# YosanoLoveButton.net
KiCad netlist of a schematic drawn in EAGLE
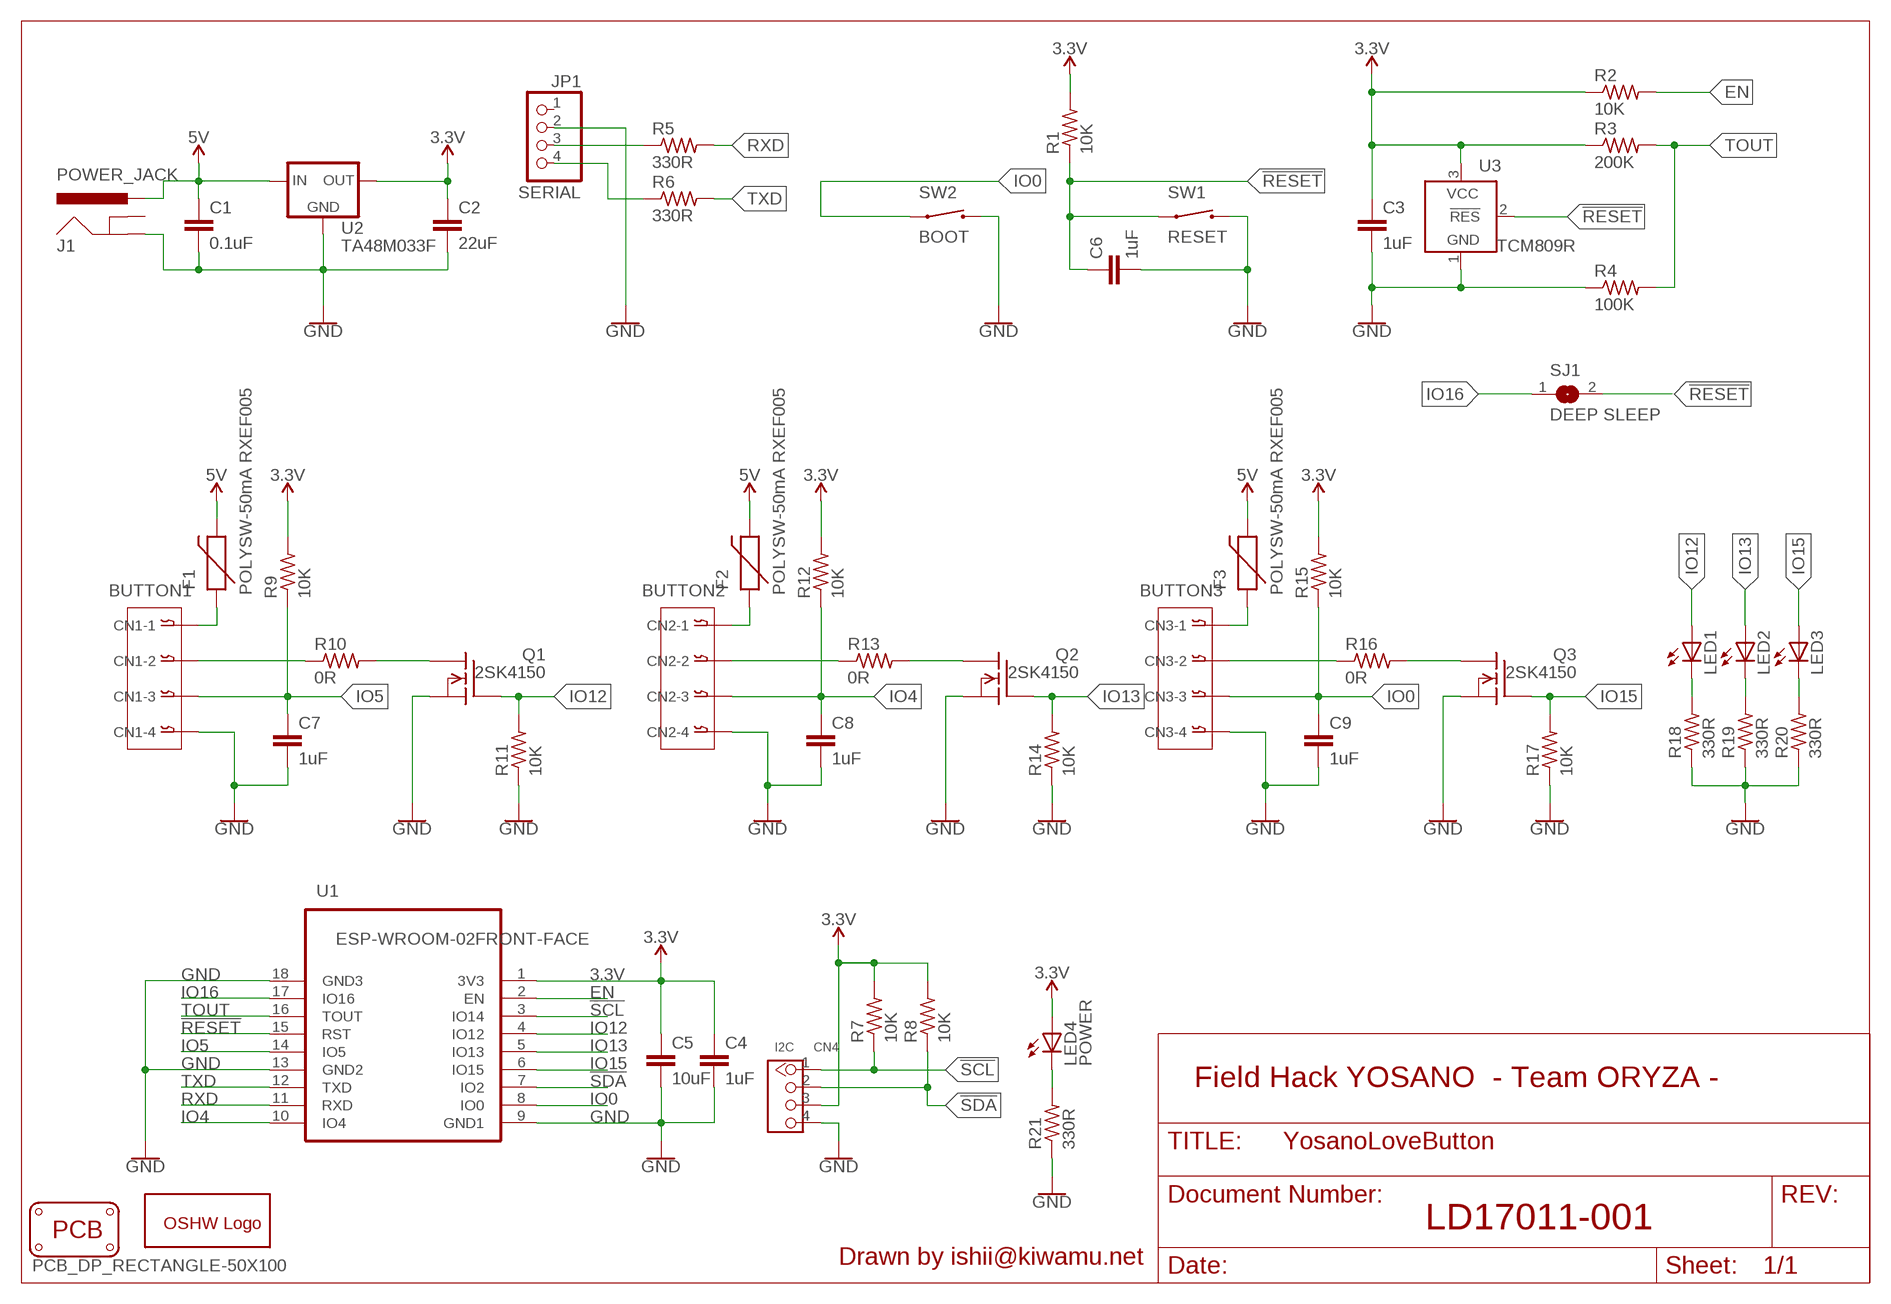
[diagram p0: schematic, sheet 1]

(export (version "E")
  (design (tool "Eeschema 10.0.6"))
  (components
    (comp (ref "C1")
      (value "0.1uF")
      (footprint "eagle-import:C5B2.5")
      (libsource (lib "eagle-import") (part "C5/2.5"))
    )
    (comp (ref "C2")
      (value "22uF")
      (footprint "eagle-import:C5B2.5")
      (libsource (lib "eagle-import") (part "C5/2.5"))
    )
    (comp (ref "C3")
      (value "1uF")
      (footprint "eagle-import:C5B2.5")
      (libsource (lib "eagle-import") (part "C5/2.5"))
    )
    (comp (ref "C4")
      (value "1uF")
      (footprint "eagle-import:C5B2.5")
      (libsource (lib "eagle-import") (part "C5/2.5"))
    )
    (comp (ref "C5")
      (value "10uF")
      (footprint "eagle-import:C5B2.5")
      (libsource (lib "eagle-import") (part "C5/2.5"))
    )
    (comp (ref "C6")
      (value "1uF")
      (footprint "eagle-import:C5B2.5")
      (libsource (lib "eagle-import") (part "C5/2.5"))
    )
    (comp (ref "C7")
      (value "1uF")
      (footprint "eagle-import:C5B2.5")
      (libsource (lib "eagle-import") (part "C5/2.5"))
    )
    (comp (ref "C8")
      (value "1uF")
      (footprint "eagle-import:C5B2.5")
      (libsource (lib "eagle-import") (part "C5/2.5"))
    )
    (comp (ref "C9")
      (value "1uF")
      (footprint "eagle-import:C5B2.5")
      (libsource (lib "eagle-import") (part "C5/2.5"))
    )
    (comp (ref "CN1")
      (value "BUTTON1")
      (footprint "eagle-import:B4B-XH")
      (libsource (lib "eagle-import") (part "04-JST-B4B-XH-A"))
    )
    (comp (ref "CN2")
      (value "BUTTON2")
      (footprint "eagle-import:B4B-XH")
      (libsource (lib "eagle-import") (part "04-JST-B4B-XH-A"))
    )
    (comp (ref "CN3")
      (value "BUTTON3")
      (footprint "eagle-import:B4B-XH")
      (libsource (lib "eagle-import") (part "04-JST-B4B-XH-A"))
    )
    (comp (ref "CN4")
      (value "I2C")
      (footprint "eagle-import:HW4-2.0")
      (libsource (lib "eagle-import") (part "GROVE-CONNECTOR-DIP(4P-2.0)"))
    )
    (comp (ref "F1")
      (value "POLYSW-50mA RXEF005")
      (footprint "eagle-import:PTC")
      (libsource (lib "eagle-import") (part "PTCPTH"))
    )
    (comp (ref "F2")
      (value "POLYSW-50mA RXEF005")
      (footprint "eagle-import:PTC")
      (libsource (lib "eagle-import") (part "PTCPTH"))
    )
    (comp (ref "F3")
      (value "POLYSW-50mA RXEF005")
      (footprint "eagle-import:PTC")
      (libsource (lib "eagle-import") (part "PTCPTH"))
    )
    (comp (ref "GOLD_ORB_SM1")
      (value "OSHWLOGOLOGO5MM")
      (footprint "eagle-import:OSHW_5MM")
      (libsource (lib "eagle-import") (part "OSHWLOGOLOGO5MM"))
    )
    (comp (ref "J1")
      (value "POWER_JACK")
      (footprint "eagle-import:POWER_JACK_PTH")
      (libsource (lib "eagle-import") (part "POWER_JACK"))
    )
    (comp (ref "JP1")
      (value "SERIAL")
      (footprint "eagle-import:1X04")
      (libsource (lib "eagle-import") (part "PINHD-1X4"))
    )
    (comp (ref "LED1")
      (value "LED3MM")
      (footprint "eagle-import:LED3MM")
      (libsource (lib "eagle-import") (part "LED3MM"))
    )
    (comp (ref "LED2")
      (value "LED3MM")
      (footprint "eagle-import:LED3MM")
      (libsource (lib "eagle-import") (part "LED3MM"))
    )
    (comp (ref "LED3")
      (value "LED3MM")
      (footprint "eagle-import:LED3MM")
      (libsource (lib "eagle-import") (part "LED3MM"))
    )
    (comp (ref "LED4")
      (value "POWER")
      (footprint "eagle-import:LED3MM")
      (libsource (lib "eagle-import") (part "LED3MM"))
    )
    (comp (ref "PCB1")
      (value "PCB_DP_RECTANGLE-50X100")
      (footprint "eagle-import:DP10050_V1")
      (libsource (lib "eagle-import") (part "PCB_DP_RECTANGLE-50X100"))
    )
    (comp (ref "Q1")
      (value "2SK4150")
      (footprint "eagle-import:TO92")
      (libsource (lib "eagle-import") (part "BSS101"))
    )
    (comp (ref "Q2")
      (value "2SK4150")
      (footprint "eagle-import:TO92")
      (libsource (lib "eagle-import") (part "BSS101"))
    )
    (comp (ref "Q3")
      (value "2SK4150")
      (footprint "eagle-import:TO92")
      (libsource (lib "eagle-import") (part "BSS101"))
    )
    (comp (ref "R1")
      (value "10K")
      (footprint "eagle-import:0204_7")
      (libsource (lib "eagle-import") (part "R-US_0204/7"))
    )
    (comp (ref "R2")
      (value "10K")
      (footprint "eagle-import:0204_7")
      (libsource (lib "eagle-import") (part "R-US_0204/7"))
    )
    (comp (ref "R3")
      (value "200K")
      (footprint "eagle-import:0204_7")
      (libsource (lib "eagle-import") (part "R-US_0204/7"))
    )
    (comp (ref "R4")
      (value "100K")
      (footprint "eagle-import:0204_7")
      (libsource (lib "eagle-import") (part "R-US_0204/7"))
    )
    (comp (ref "R5")
      (value "330R")
      (footprint "eagle-import:0204_7")
      (libsource (lib "eagle-import") (part "R-US_0204/7"))
    )
    (comp (ref "R6")
      (value "330R")
      (footprint "eagle-import:0204_7")
      (libsource (lib "eagle-import") (part "R-US_0204/7"))
    )
    (comp (ref "R7")
      (value "10K")
      (footprint "eagle-import:0204_7")
      (libsource (lib "eagle-import") (part "R-US_0204/7"))
    )
    (comp (ref "R8")
      (value "10K")
      (footprint "eagle-import:0204_7")
      (libsource (lib "eagle-import") (part "R-US_0204/7"))
    )
    (comp (ref "R9")
      (value "10K")
      (footprint "eagle-import:0204_7")
      (libsource (lib "eagle-import") (part "R-US_0204/7"))
    )
    (comp (ref "R10")
      (value "0R")
      (footprint "eagle-import:0204_7")
      (libsource (lib "eagle-import") (part "R-US_0204/7"))
    )
    (comp (ref "R11")
      (value "10K")
      (footprint "eagle-import:0204_7")
      (libsource (lib "eagle-import") (part "R-US_0204/7"))
    )
    (comp (ref "R12")
      (value "10K")
      (footprint "eagle-import:0204_7")
      (libsource (lib "eagle-import") (part "R-US_0204/7"))
    )
    (comp (ref "R13")
      (value "0R")
      (footprint "eagle-import:0204_7")
      (libsource (lib "eagle-import") (part "R-US_0204/7"))
    )
    (comp (ref "R14")
      (value "10K")
      (footprint "eagle-import:0204_7")
      (libsource (lib "eagle-import") (part "R-US_0204/7"))
    )
    (comp (ref "R15")
      (value "10K")
      (footprint "eagle-import:0204_7")
      (libsource (lib "eagle-import") (part "R-US_0204/7"))
    )
    (comp (ref "R16")
      (value "0R")
      (footprint "eagle-import:0204_7")
      (libsource (lib "eagle-import") (part "R-US_0204/7"))
    )
    (comp (ref "R17")
      (value "10K")
      (footprint "eagle-import:0204_7")
      (libsource (lib "eagle-import") (part "R-US_0204/7"))
    )
    (comp (ref "R18")
      (value "330R")
      (footprint "eagle-import:0204_7")
      (libsource (lib "eagle-import") (part "R-US_0204/7"))
    )
    (comp (ref "R19")
      (value "330R")
      (footprint "eagle-import:0204_7")
      (libsource (lib "eagle-import") (part "R-US_0204/7"))
    )
    (comp (ref "R20")
      (value "330R")
      (footprint "eagle-import:0204_7")
      (libsource (lib "eagle-import") (part "R-US_0204/7"))
    )
    (comp (ref "R21")
      (value "330R")
      (footprint "eagle-import:0204_7")
      (libsource (lib "eagle-import") (part "R-US_0204/7"))
    )
    (comp (ref "SJ1")
      (value "DEEP SLEEP")
      (footprint "eagle-import:SOLDERJUMPER_REFLOW")
      (libsource (lib "eagle-import") (part "SOLDERJUMPERREFLOW"))
    )
    (comp (ref "SW1")
      (value "RESET")
      (footprint "eagle-import:TVBP06")
      (libsource (lib "eagle-import") (part "TVBP06"))
    )
    (comp (ref "SW2")
      (value "BOOT")
      (footprint "eagle-import:TVBP06")
      (libsource (lib "eagle-import") (part "TVBP06"))
    )
    (comp (ref "U1")
      (value "ESP-WROOM-02FRONT-FACE")
      (footprint "eagle-import:FRONT-FACE")
      (libsource (lib "eagle-import") (part "ESP-WROOM-02FRONT-FACE"))
    )
    (comp (ref "U2")
      (value "TA48M033F")
      (footprint "eagle-import:DPACK")
      (libsource (lib "eagle-import") (part "TA48?M033F"))
    )
    (comp (ref "U3")
      (value "TCM809R")
      (footprint "eagle-import:SOT23B-3")
      (fields (field (name "MF") "MICROCHIP") (field (name "MPN") "TCM809MENB713"))
      (libsource (lib "eagle-import") (part "TCM809"))
    )
  )
  (nets
    (net (code "1") (name "/~{RESET}") (class "Default")
      (node (ref "C6") (pin "1") (pinfunction "1_1") (pintype "passive"))
      (node (ref "R1") (pin "1") (pinfunction "1_1") (pintype "passive"))
      (node (ref "SJ1") (pin "2") (pinfunction "2_2") (pintype "passive"))
      (node (ref "SW1") (pin "1") (pinfunction "1_1") (pintype "passive"))
      (node (ref "U1") (pin "15") (pinfunction "RST_15") (pintype "bidirectional"))
      (node (ref "U3") (pin "2") (pinfunction "~{RES}_2") (pintype "output"))
    )
    (net (code "2") (name "/~{SCL}") (class "Default")
      (node (ref "CN4") (pin "1") (pinfunction "1_1") (pintype "bidirectional"))
      (node (ref "R7") (pin "1") (pinfunction "1_1") (pintype "passive"))
      (node (ref "U1") (pin "3") (pinfunction "IO14_3") (pintype "bidirectional"))
    )
    (net (code "3") (name "/~{SDA}") (class "Default")
      (node (ref "CN4") (pin "2") (pinfunction "2_2") (pintype "bidirectional"))
      (node (ref "R8") (pin "1") (pinfunction "1_1") (pintype "passive"))
      (node (ref "U1") (pin "7") (pinfunction "IO2_7") (pintype "bidirectional"))
    )
    (net (code "4") (name "3.3V") (class "Default")
      (node (ref "C2") (pin "1") (pinfunction "1_1") (pintype "passive"))
      (node (ref "C3") (pin "1") (pinfunction "1_1") (pintype "passive"))
      (node (ref "C4") (pin "1") (pinfunction "1_1") (pintype "passive"))
      (node (ref "C5") (pin "1") (pinfunction "1_1") (pintype "passive"))
      (node (ref "CN4") (pin "3") (pinfunction "3_3") (pintype "bidirectional"))
      (node (ref "LED4") (pin "A") (pinfunction "A_A") (pintype "passive"))
      (node (ref "R1") (pin "2") (pinfunction "2_2") (pintype "passive"))
      (node (ref "R12") (pin "2") (pinfunction "2_2") (pintype "passive"))
      (node (ref "R15") (pin "2") (pinfunction "2_2") (pintype "passive"))
      (node (ref "R2") (pin "1") (pinfunction "1_1") (pintype "passive"))
      (node (ref "R3") (pin "1") (pinfunction "1_1") (pintype "passive"))
      (node (ref "R7") (pin "2") (pinfunction "2_2") (pintype "passive"))
      (node (ref "R8") (pin "2") (pinfunction "2_2") (pintype "passive"))
      (node (ref "R9") (pin "2") (pinfunction "2_2") (pintype "passive"))
      (node (ref "U1") (pin "1") (pinfunction "3V3_1") (pintype "power_in"))
      (node (ref "U2") (pin "3") (pinfunction "OUT_3") (pintype "passive"))
      (node (ref "U3") (pin "3") (pinfunction "VCC_3") (pintype "power_in"))
    )
    (net (code "5") (name "5V") (class "Default")
      (node (ref "C1") (pin "1") (pinfunction "1_1") (pintype "passive"))
      (node (ref "F1") (pin "P$2") (pinfunction "2_P$2") (pintype "bidirectional"))
      (node (ref "F2") (pin "P$2") (pinfunction "2_P$2") (pintype "bidirectional"))
      (node (ref "F3") (pin "P$2") (pinfunction "2_P$2") (pintype "bidirectional"))
      (node (ref "J1") (pin "PWR") (pinfunction "PWR_PWR") (pintype "bidirectional"))
      (node (ref "U2") (pin "1") (pinfunction "IN_1") (pintype "input"))
    )
    (net (code "6") (name "EN") (class "Default")
      (node (ref "R2") (pin "2") (pinfunction "2_2") (pintype "passive"))
      (node (ref "U1") (pin "2") (pinfunction "EN_2") (pintype "bidirectional"))
    )
    (net (code "7") (name "GND") (class "Default")
      (node (ref "C1") (pin "2") (pinfunction "2_2") (pintype "passive"))
      (node (ref "C2") (pin "2") (pinfunction "2_2") (pintype "passive"))
      (node (ref "C3") (pin "2") (pinfunction "2_2") (pintype "passive"))
      (node (ref "C4") (pin "2") (pinfunction "2_2") (pintype "passive"))
      (node (ref "C5") (pin "2") (pinfunction "2_2") (pintype "passive"))
      (node (ref "C6") (pin "2") (pinfunction "2_2") (pintype "passive"))
      (node (ref "C7") (pin "2") (pinfunction "2_2") (pintype "passive"))
      (node (ref "C8") (pin "2") (pinfunction "2_2") (pintype "passive"))
      (node (ref "C9") (pin "2") (pinfunction "2_2") (pintype "passive"))
      (node (ref "CN1") (pin "P$4") (pinfunction "1_P$4") (pintype "passive"))
      (node (ref "CN2") (pin "P$4") (pinfunction "1_P$4") (pintype "passive"))
      (node (ref "CN3") (pin "P$4") (pinfunction "1_P$4") (pintype "passive"))
      (node (ref "CN4") (pin "4") (pinfunction "4_4") (pintype "bidirectional"))
      (node (ref "J1") (pin "GND") (pinfunction "GND_GND") (pintype "bidirectional"))
      (node (ref "JP1") (pin "2") (pinfunction "2_2") (pintype "passive"))
      (node (ref "Q1") (pin "1") (pinfunction "S_1") (pintype "passive"))
      (node (ref "Q2") (pin "1") (pinfunction "S_1") (pintype "passive"))
      (node (ref "Q3") (pin "1") (pinfunction "S_1") (pintype "passive"))
      (node (ref "R11") (pin "1") (pinfunction "1_1") (pintype "passive"))
      (node (ref "R14") (pin "1") (pinfunction "1_1") (pintype "passive"))
      (node (ref "R17") (pin "1") (pinfunction "1_1") (pintype "passive"))
      (node (ref "R18") (pin "1") (pinfunction "1_1") (pintype "passive"))
      (node (ref "R19") (pin "1") (pinfunction "1_1") (pintype "passive"))
      (node (ref "R20") (pin "1") (pinfunction "1_1") (pintype "passive"))
      (node (ref "R21") (pin "1") (pinfunction "1_1") (pintype "passive"))
      (node (ref "R4") (pin "1") (pinfunction "1_1") (pintype "passive"))
      (node (ref "SW1") (pin "2") (pinfunction "2_2") (pintype "passive"))
      (node (ref "SW2") (pin "2") (pinfunction "2_2") (pintype "passive"))
      (node (ref "U1") (pin "13") (pinfunction "GND2_13") (pintype "power_in"))
      (node (ref "U1") (pin "18") (pinfunction "GND3_18") (pintype "power_in"))
      (node (ref "U1") (pin "9") (pinfunction "GND1_9") (pintype "power_in"))
      (node (ref "U2") (pin "4") (pinfunction "GND_4") (pintype "power_in"))
      (node (ref "U3") (pin "1") (pinfunction "GND_1") (pintype "power_in"))
    )
    (net (code "8") (name "IO0") (class "Default")
      (node (ref "C9") (pin "1") (pinfunction "1_1") (pintype "passive"))
      (node (ref "CN3") (pin "P$3") (pinfunction "1_P$3") (pintype "passive"))
      (node (ref "R15") (pin "1") (pinfunction "1_1") (pintype "passive"))
      (node (ref "SW2") (pin "1") (pinfunction "1_1") (pintype "passive"))
      (node (ref "U1") (pin "8") (pinfunction "IO0_8") (pintype "bidirectional"))
    )
    (net (code "9") (name "IO4") (class "Default")
      (node (ref "C8") (pin "1") (pinfunction "1_1") (pintype "passive"))
      (node (ref "CN2") (pin "P$3") (pinfunction "1_P$3") (pintype "passive"))
      (node (ref "R12") (pin "1") (pinfunction "1_1") (pintype "passive"))
      (node (ref "U1") (pin "10") (pinfunction "IO4_10") (pintype "bidirectional"))
    )
    (net (code "10") (name "IO5") (class "Default")
      (node (ref "C7") (pin "1") (pinfunction "1_1") (pintype "passive"))
      (node (ref "CN1") (pin "P$3") (pinfunction "1_P$3") (pintype "passive"))
      (node (ref "R9") (pin "1") (pinfunction "1_1") (pintype "passive"))
      (node (ref "U1") (pin "14") (pinfunction "IO5_14") (pintype "open_collector"))
    )
    (net (code "11") (name "IO12") (class "Default")
      (node (ref "LED1") (pin "A") (pinfunction "A_A") (pintype "passive"))
      (node (ref "Q1") (pin "2") (pinfunction "G_2") (pintype "passive"))
      (node (ref "R11") (pin "2") (pinfunction "2_2") (pintype "passive"))
      (node (ref "U1") (pin "4") (pinfunction "IO12_4") (pintype "bidirectional"))
    )
    (net (code "12") (name "IO13") (class "Default")
      (node (ref "LED2") (pin "A") (pinfunction "A_A") (pintype "passive"))
      (node (ref "Q2") (pin "2") (pinfunction "G_2") (pintype "passive"))
      (node (ref "R14") (pin "2") (pinfunction "2_2") (pintype "passive"))
      (node (ref "U1") (pin "5") (pinfunction "IO13_5") (pintype "bidirectional"))
    )
    (net (code "13") (name "IO15") (class "Default")
      (node (ref "LED3") (pin "A") (pinfunction "A_A") (pintype "passive"))
      (node (ref "Q3") (pin "2") (pinfunction "G_2") (pintype "passive"))
      (node (ref "R17") (pin "2") (pinfunction "2_2") (pintype "passive"))
      (node (ref "U1") (pin "6") (pinfunction "IO15_6") (pintype "bidirectional"))
    )
    (net (code "14") (name "IO16") (class "Default")
      (node (ref "SJ1") (pin "1") (pinfunction "1_1") (pintype "passive"))
      (node (ref "U1") (pin "17") (pinfunction "IO16_17") (pintype "bidirectional"))
    )
    (net (code "15") (name "Net-(CN1A-1)") (class "Default")
      (node (ref "CN1") (pin "P$1") (pinfunction "1_P$1") (pintype "passive"))
      (node (ref "F1") (pin "P$1") (pinfunction "1_P$1") (pintype "bidirectional"))
    )
    (net (code "16") (name "Net-(CN1B-1)") (class "Default")
      (node (ref "CN1") (pin "P$2") (pinfunction "1_P$2") (pintype "passive"))
      (node (ref "R10") (pin "1") (pinfunction "1_1") (pintype "passive"))
    )
    (net (code "17") (name "Net-(CN2A-1)") (class "Default")
      (node (ref "CN2") (pin "P$1") (pinfunction "1_P$1") (pintype "passive"))
      (node (ref "F2") (pin "P$1") (pinfunction "1_P$1") (pintype "bidirectional"))
    )
    (net (code "18") (name "Net-(CN2B-1)") (class "Default")
      (node (ref "CN2") (pin "P$2") (pinfunction "1_P$2") (pintype "passive"))
      (node (ref "R13") (pin "1") (pinfunction "1_1") (pintype "passive"))
    )
    (net (code "19") (name "Net-(CN3A-1)") (class "Default")
      (node (ref "CN3") (pin "P$1") (pinfunction "1_P$1") (pintype "passive"))
      (node (ref "F3") (pin "P$1") (pinfunction "1_P$1") (pintype "bidirectional"))
    )
    (net (code "20") (name "Net-(CN3B-1)") (class "Default")
      (node (ref "CN3") (pin "P$2") (pinfunction "1_P$2") (pintype "passive"))
      (node (ref "R16") (pin "1") (pinfunction "1_1") (pintype "passive"))
    )
    (net (code "21") (name "Net-(JP1-Pad3)") (class "Default")
      (node (ref "JP1") (pin "3") (pinfunction "3_3") (pintype "passive"))
      (node (ref "R5") (pin "1") (pinfunction "1_1") (pintype "passive"))
    )
    (net (code "22") (name "Net-(JP1-Pad4)") (class "Default")
      (node (ref "JP1") (pin "4") (pinfunction "4_4") (pintype "passive"))
      (node (ref "R6") (pin "1") (pinfunction "1_1") (pintype "passive"))
    )
    (net (code "23") (name "Net-(LED1-C)") (class "Default")
      (node (ref "LED1") (pin "K") (pinfunction "C_K") (pintype "passive"))
      (node (ref "R18") (pin "2") (pinfunction "2_2") (pintype "passive"))
    )
    (net (code "24") (name "Net-(LED2-C)") (class "Default")
      (node (ref "LED2") (pin "K") (pinfunction "C_K") (pintype "passive"))
      (node (ref "R19") (pin "2") (pinfunction "2_2") (pintype "passive"))
    )
    (net (code "25") (name "Net-(LED3-C)") (class "Default")
      (node (ref "LED3") (pin "K") (pinfunction "C_K") (pintype "passive"))
      (node (ref "R20") (pin "2") (pinfunction "2_2") (pintype "passive"))
    )
    (net (code "26") (name "Net-(LED4-C)") (class "Default")
      (node (ref "LED4") (pin "K") (pinfunction "C_K") (pintype "passive"))
      (node (ref "R21") (pin "2") (pinfunction "2_2") (pintype "passive"))
    )
    (net (code "27") (name "Net-(Q1-D)") (class "Default")
      (node (ref "Q1") (pin "3") (pinfunction "D_3") (pintype "passive"))
      (node (ref "R10") (pin "2") (pinfunction "2_2") (pintype "passive"))
    )
    (net (code "28") (name "Net-(Q2-D)") (class "Default")
      (node (ref "Q2") (pin "3") (pinfunction "D_3") (pintype "passive"))
      (node (ref "R13") (pin "2") (pinfunction "2_2") (pintype "passive"))
    )
    (net (code "29") (name "Net-(Q3-D)") (class "Default")
      (node (ref "Q3") (pin "3") (pinfunction "D_3") (pintype "passive"))
      (node (ref "R16") (pin "2") (pinfunction "2_2") (pintype "passive"))
    )
    (net (code "30") (name "RXD") (class "Default")
      (node (ref "R5") (pin "2") (pinfunction "2_2") (pintype "passive"))
      (node (ref "U1") (pin "11") (pinfunction "RXD_11") (pintype "bidirectional"))
    )
    (net (code "31") (name "TOUT") (class "Default")
      (node (ref "R3") (pin "2") (pinfunction "2_2") (pintype "passive"))
      (node (ref "R4") (pin "2") (pinfunction "2_2") (pintype "passive"))
      (node (ref "U1") (pin "16") (pinfunction "TOUT_16") (pintype "bidirectional"))
    )
    (net (code "32") (name "TXD") (class "Default")
      (node (ref "R6") (pin "2") (pinfunction "2_2") (pintype "passive"))
      (node (ref "U1") (pin "12") (pinfunction "TXD_12") (pintype "bidirectional"))
    )
    (net (code "33") (name "unconnected-(J1-PadGNDBREAK)") (class "Default")
      (node (ref "J1") (pin "GNDBREAK") (pinfunction "GNDBREAK_GNDBREAK") (pintype "bidirectional"))
    )
    (net (code "34") (name "unconnected-(JP1-Pad1)") (class "Default")
      (node (ref "JP1") (pin "1") (pinfunction "1_1") (pintype "passive"))
    )
  )
)
